# circuit_R2.net
KiCad netlist of a schematic drawn in EAGLE
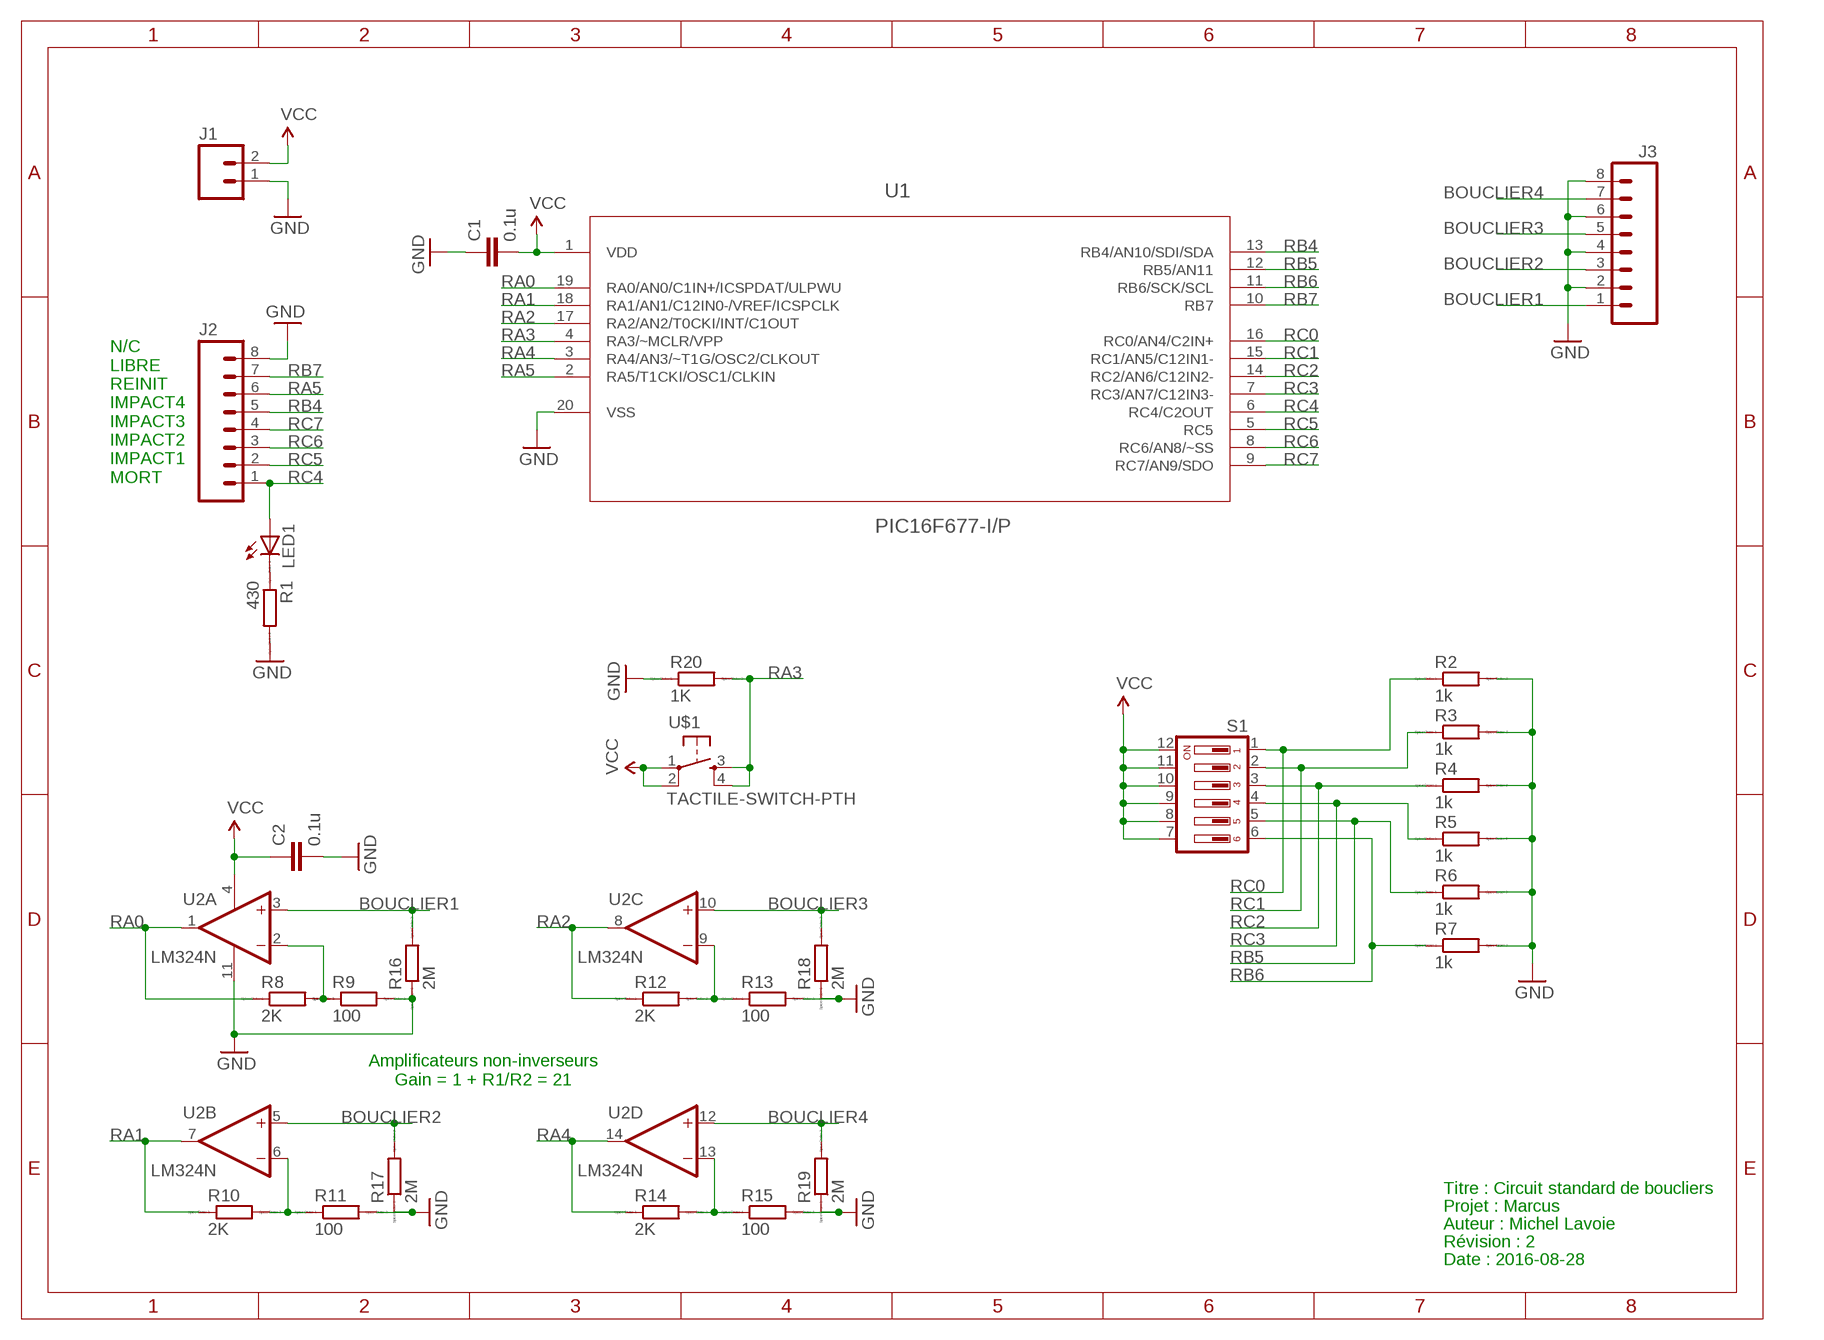
[diagram p0: schematic, sheet 1]

(export (version "E")
  (design (tool "Eeschema 10.0.6"))
  (components
    (comp (ref "C1")
      (value "0.1u")
      (footprint "eagle-import:CAP-PTH-SMALL")
      (libsource (lib "eagle-import") (part "CAPPTH"))
    )
    (comp (ref "C2")
      (value "0.1u")
      (footprint "eagle-import:CAP-PTH-SMALL")
      (libsource (lib "eagle-import") (part "CAPPTH"))
    )
    (comp (ref "J1")
      (value "M02PTH")
      (footprint "eagle-import:1X02")
      (libsource (lib "eagle-import") (part "M02PTH"))
    )
    (comp (ref "J2")
      (value "M08NO_SILK")
      (footprint "eagle-import:1X08_PIN1_NO_SILK")
      (libsource (lib "eagle-import") (part "M08NO_SILK"))
    )
    (comp (ref "J3")
      (value "M08NO_SILK")
      (footprint "eagle-import:1X08_PIN1_NO_SILK")
      (libsource (lib "eagle-import") (part "M08NO_SILK"))
    )
    (comp (ref "LED1")
      (value "LED3MM")
      (footprint "eagle-import:LED3MM")
      (libsource (lib "eagle-import") (part "LED3MM"))
    )
    (comp (ref "R1")
      (value "430")
      (footprint "eagle-import:0207_10")
      (libsource (lib "eagle-import") (part "R0207/10"))
    )
    (comp (ref "R2")
      (value "1k")
      (footprint "eagle-import:0207_10")
      (libsource (lib "eagle-import") (part "R0207/10"))
    )
    (comp (ref "R3")
      (value "1k")
      (footprint "eagle-import:0207_10")
      (libsource (lib "eagle-import") (part "R0207/10"))
    )
    (comp (ref "R4")
      (value "1k")
      (footprint "eagle-import:0207_10")
      (libsource (lib "eagle-import") (part "R0207/10"))
    )
    (comp (ref "R5")
      (value "1k")
      (footprint "eagle-import:0207_10")
      (libsource (lib "eagle-import") (part "R0207/10"))
    )
    (comp (ref "R6")
      (value "1k")
      (footprint "eagle-import:0207_10")
      (libsource (lib "eagle-import") (part "R0207/10"))
    )
    (comp (ref "R7")
      (value "1k")
      (footprint "eagle-import:0207_10")
      (libsource (lib "eagle-import") (part "R0207/10"))
    )
    (comp (ref "R8")
      (value "2K")
      (footprint "eagle-import:0207_10")
      (libsource (lib "eagle-import") (part "R0207/10"))
    )
    (comp (ref "R9")
      (value "100")
      (footprint "eagle-import:0207_10")
      (libsource (lib "eagle-import") (part "R0207/10"))
    )
    (comp (ref "R10")
      (value "2K")
      (footprint "eagle-import:0207_10")
      (libsource (lib "eagle-import") (part "R0207/10"))
    )
    (comp (ref "R11")
      (value "100")
      (footprint "eagle-import:0207_10")
      (libsource (lib "eagle-import") (part "R0207/10"))
    )
    (comp (ref "R12")
      (value "2K")
      (footprint "eagle-import:0207_10")
      (libsource (lib "eagle-import") (part "R0207/10"))
    )
    (comp (ref "R13")
      (value "100")
      (footprint "eagle-import:0207_10")
      (libsource (lib "eagle-import") (part "R0207/10"))
    )
    (comp (ref "R14")
      (value "2K")
      (footprint "eagle-import:0207_10")
      (libsource (lib "eagle-import") (part "R0207/10"))
    )
    (comp (ref "R15")
      (value "100")
      (footprint "eagle-import:0207_10")
      (libsource (lib "eagle-import") (part "R0207/10"))
    )
    (comp (ref "R16")
      (value "2M")
      (footprint "eagle-import:0207_10")
      (libsource (lib "eagle-import") (part "R0207/10"))
    )
    (comp (ref "R17")
      (value "2M")
      (footprint "eagle-import:0207_10")
      (libsource (lib "eagle-import") (part "R0207/10"))
    )
    (comp (ref "R18")
      (value "2M")
      (footprint "eagle-import:0207_10")
      (libsource (lib "eagle-import") (part "R0207/10"))
    )
    (comp (ref "R19")
      (value "2M")
      (footprint "eagle-import:0207_10")
      (libsource (lib "eagle-import") (part "R0207/10"))
    )
    (comp (ref "R20")
      (value "1K")
      (footprint "eagle-import:0207_10")
      (libsource (lib "eagle-import") (part "R0207/10"))
    )
    (comp (ref "S1")
      (value "DIP06YL")
      (footprint "eagle-import:DIP06YL")
      (libsource (lib "eagle-import") (part "DIP06YL"))
    )
    (comp (ref "U$1")
      (value "TACTILE-SWITCH-PTH")
      (footprint "eagle-import:TAC-SWITCH-PTH")
      (libsource (lib "eagle-import") (part "TACTILE-SWITCH-PTH"))
    )
    (comp (ref "U1")
      (value "PIC16F677-I/P")
      (footprint "eagle-import:DIP254P762X533-20")
      (libsource (lib "eagle-import") (part "PIC16F677-I/P"))
    )
    (comp (ref "U2")
      (value "LM324N")
      (footprint "eagle-import:DIL14")
      (libsource (lib "eagle-import") (part "LM324N"))
    )
  )
  (nets
    (net (code "1") (name "/BOUCLIER1") (class "Default")
      (node (ref "J3") (pin "1") (pinfunction "1_1") (pintype "passive"))
      (node (ref "R16") (pin "2") (pinfunction "2_2") (pintype "passive"))
      (node (ref "U2") (pin "3") (pinfunction "+IN_3") (pintype "input"))
    )
    (net (code "2") (name "/BOUCLIER2") (class "Default")
      (node (ref "J3") (pin "3") (pinfunction "3_3") (pintype "passive"))
      (node (ref "R17") (pin "2") (pinfunction "2_2") (pintype "passive"))
      (node (ref "U2") (pin "5") (pinfunction "+IN_5") (pintype "input"))
    )
    (net (code "3") (name "/BOUCLIER3") (class "Default")
      (node (ref "J3") (pin "5") (pinfunction "5_5") (pintype "passive"))
      (node (ref "R18") (pin "2") (pinfunction "2_2") (pintype "passive"))
      (node (ref "U2") (pin "10") (pinfunction "+IN_10") (pintype "input"))
    )
    (net (code "4") (name "/BOUCLIER4") (class "Default")
      (node (ref "J3") (pin "7") (pinfunction "7_7") (pintype "passive"))
      (node (ref "R19") (pin "2") (pinfunction "2_2") (pintype "passive"))
      (node (ref "U2") (pin "12") (pinfunction "+IN_12") (pintype "input"))
    )
    (net (code "5") (name "/RA0") (class "Default")
      (node (ref "R8") (pin "1") (pinfunction "1_1") (pintype "passive"))
      (node (ref "U1") (pin "19") (pinfunction "RA0/AN0/C1IN+/ICSPDAT/ULPWU_19") (pintype "bidirectional"))
      (node (ref "U2") (pin "1") (pinfunction "OUT_1") (pintype "output"))
    )
    (net (code "6") (name "/RA1") (class "Default")
      (node (ref "R10") (pin "1") (pinfunction "1_1") (pintype "passive"))
      (node (ref "U1") (pin "18") (pinfunction "RA1/AN1/C12IN0-/VREF/ICSPCLK_18") (pintype "bidirectional"))
      (node (ref "U2") (pin "7") (pinfunction "OUT_7") (pintype "output"))
    )
    (net (code "7") (name "/RA2") (class "Default")
      (node (ref "R12") (pin "1") (pinfunction "1_1") (pintype "passive"))
      (node (ref "U1") (pin "17") (pinfunction "RA2/AN2/T0CKI/INT/C1OUT_17") (pintype "bidirectional"))
      (node (ref "U2") (pin "8") (pinfunction "OUT_8") (pintype "output"))
    )
    (net (code "8") (name "/RA3") (class "Default")
      (node (ref "R20") (pin "2") (pinfunction "2_2") (pintype "passive"))
      (node (ref "U$1") (pin "3") (pinfunction "3_3") (pintype "passive"))
      (node (ref "U$1") (pin "4") (pinfunction "4_4") (pintype "passive"))
      (node (ref "U1") (pin "4") (pinfunction "RA3/~{MCLR/VPP}_4") (pintype "bidirectional"))
    )
    (net (code "9") (name "/RA4") (class "Default")
      (node (ref "R14") (pin "1") (pinfunction "1_1") (pintype "passive"))
      (node (ref "U1") (pin "3") (pinfunction "RA4/AN3/~{T1G/OSC2/CLKOUT}_3") (pintype "bidirectional"))
      (node (ref "U2") (pin "14") (pinfunction "OUT_14") (pintype "output"))
    )
    (net (code "10") (name "/RA5") (class "Default")
      (node (ref "J2") (pin "6") (pinfunction "6_6") (pintype "passive"))
      (node (ref "U1") (pin "2") (pinfunction "RA5/T1CKI/OSC1/CLKIN_2") (pintype "bidirectional"))
    )
    (net (code "11") (name "/RB4") (class "Default")
      (node (ref "J2") (pin "5") (pinfunction "5_5") (pintype "passive"))
      (node (ref "U1") (pin "13") (pinfunction "RB4/AN10/SDI/SDA_13") (pintype "bidirectional"))
    )
    (net (code "12") (name "/RB5") (class "Default")
      (node (ref "R6") (pin "1") (pinfunction "1_1") (pintype "passive"))
      (node (ref "S1") (pin "5") (pinfunction "5_5") (pintype "passive"))
      (node (ref "U1") (pin "12") (pinfunction "RB5/AN11_12") (pintype "bidirectional"))
    )
    (net (code "13") (name "/RB6") (class "Default")
      (node (ref "R7") (pin "1") (pinfunction "1_1") (pintype "passive"))
      (node (ref "S1") (pin "6") (pinfunction "6_6") (pintype "passive"))
      (node (ref "U1") (pin "11") (pinfunction "RB6/SCK/SCL_11") (pintype "bidirectional"))
    )
    (net (code "14") (name "/RB7") (class "Default")
      (node (ref "J2") (pin "7") (pinfunction "7_7") (pintype "passive"))
      (node (ref "U1") (pin "10") (pinfunction "RB7_10") (pintype "bidirectional"))
    )
    (net (code "15") (name "/RC0") (class "Default")
      (node (ref "R2") (pin "1") (pinfunction "1_1") (pintype "passive"))
      (node (ref "S1") (pin "1") (pinfunction "1_1") (pintype "passive"))
      (node (ref "U1") (pin "16") (pinfunction "RC0/AN4/C2IN+_16") (pintype "bidirectional"))
    )
    (net (code "16") (name "/RC1") (class "Default")
      (node (ref "R3") (pin "1") (pinfunction "1_1") (pintype "passive"))
      (node (ref "S1") (pin "2") (pinfunction "2_2") (pintype "passive"))
      (node (ref "U1") (pin "15") (pinfunction "RC1/AN5/C12IN1-_15") (pintype "bidirectional"))
    )
    (net (code "17") (name "/RC2") (class "Default")
      (node (ref "R4") (pin "1") (pinfunction "1_1") (pintype "passive"))
      (node (ref "S1") (pin "3") (pinfunction "3_3") (pintype "passive"))
      (node (ref "U1") (pin "14") (pinfunction "RC2/AN6/C12IN2-_14") (pintype "bidirectional"))
    )
    (net (code "18") (name "/RC3") (class "Default")
      (node (ref "R5") (pin "1") (pinfunction "1_1") (pintype "passive"))
      (node (ref "S1") (pin "4") (pinfunction "4_4") (pintype "passive"))
      (node (ref "U1") (pin "7") (pinfunction "RC3/AN7/C12IN3-_7") (pintype "bidirectional"))
    )
    (net (code "19") (name "/RC4") (class "Default")
      (node (ref "J2") (pin "1") (pinfunction "1_1") (pintype "passive"))
      (node (ref "LED1") (pin "A") (pinfunction "A_A") (pintype "passive"))
      (node (ref "U1") (pin "6") (pinfunction "RC4/C2OUT_6") (pintype "bidirectional"))
    )
    (net (code "20") (name "/RC5") (class "Default")
      (node (ref "J2") (pin "2") (pinfunction "2_2") (pintype "passive"))
      (node (ref "U1") (pin "5") (pinfunction "RC5_5") (pintype "bidirectional"))
    )
    (net (code "21") (name "/RC6") (class "Default")
      (node (ref "J2") (pin "3") (pinfunction "3_3") (pintype "passive"))
      (node (ref "U1") (pin "8") (pinfunction "RC6/AN8/~{SS}_8") (pintype "bidirectional"))
    )
    (net (code "22") (name "/RC7") (class "Default")
      (node (ref "J2") (pin "4") (pinfunction "4_4") (pintype "passive"))
      (node (ref "U1") (pin "9") (pinfunction "RC7/AN9/SDO_9") (pintype "bidirectional"))
    )
    (net (code "23") (name "GND") (class "Default")
      (node (ref "C1") (pin "1") (pinfunction "1_1") (pintype "passive"))
      (node (ref "C2") (pin "2") (pinfunction "2_2") (pintype "passive"))
      (node (ref "J1") (pin "1") (pinfunction "1_1") (pintype "passive"))
      (node (ref "J2") (pin "8") (pinfunction "8_8") (pintype "passive"))
      (node (ref "J3") (pin "2") (pinfunction "2_2") (pintype "passive"))
      (node (ref "J3") (pin "4") (pinfunction "4_4") (pintype "passive"))
      (node (ref "J3") (pin "6") (pinfunction "6_6") (pintype "passive"))
      (node (ref "J3") (pin "8") (pinfunction "8_8") (pintype "passive"))
      (node (ref "R1") (pin "2") (pinfunction "2_2") (pintype "passive"))
      (node (ref "R11") (pin "2") (pinfunction "2_2") (pintype "passive"))
      (node (ref "R13") (pin "2") (pinfunction "2_2") (pintype "passive"))
      (node (ref "R15") (pin "2") (pinfunction "2_2") (pintype "passive"))
      (node (ref "R16") (pin "1") (pinfunction "1_1") (pintype "passive"))
      (node (ref "R17") (pin "1") (pinfunction "1_1") (pintype "passive"))
      (node (ref "R18") (pin "1") (pinfunction "1_1") (pintype "passive"))
      (node (ref "R19") (pin "1") (pinfunction "1_1") (pintype "passive"))
      (node (ref "R2") (pin "2") (pinfunction "2_2") (pintype "passive"))
      (node (ref "R20") (pin "1") (pinfunction "1_1") (pintype "passive"))
      (node (ref "R3") (pin "2") (pinfunction "2_2") (pintype "passive"))
      (node (ref "R4") (pin "2") (pinfunction "2_2") (pintype "passive"))
      (node (ref "R5") (pin "2") (pinfunction "2_2") (pintype "passive"))
      (node (ref "R6") (pin "2") (pinfunction "2_2") (pintype "passive"))
      (node (ref "R7") (pin "2") (pinfunction "2_2") (pintype "passive"))
      (node (ref "R9") (pin "2") (pinfunction "2_2") (pintype "passive"))
      (node (ref "U1") (pin "20") (pinfunction "VSS_20") (pintype "power_in"))
      (node (ref "U2") (pin "11") (pinfunction "V-_11") (pintype "power_in"))
    )
    (net (code "24") (name "Net-(LED1-C)") (class "Default")
      (node (ref "LED1") (pin "K") (pinfunction "C_K") (pintype "passive"))
      (node (ref "R1") (pin "1") (pinfunction "1_1") (pintype "passive"))
    )
    (net (code "25") (name "Net-(U2A--IN)") (class "Default")
      (node (ref "R8") (pin "2") (pinfunction "2_2") (pintype "passive"))
      (node (ref "R9") (pin "1") (pinfunction "1_1") (pintype "passive"))
      (node (ref "U2") (pin "2") (pinfunction "-IN_2") (pintype "input"))
    )
    (net (code "26") (name "Net-(U2B--IN)") (class "Default")
      (node (ref "R10") (pin "2") (pinfunction "2_2") (pintype "passive"))
      (node (ref "R11") (pin "1") (pinfunction "1_1") (pintype "passive"))
      (node (ref "U2") (pin "6") (pinfunction "-IN_6") (pintype "input"))
    )
    (net (code "27") (name "Net-(U2C--IN)") (class "Default")
      (node (ref "R12") (pin "2") (pinfunction "2_2") (pintype "passive"))
      (node (ref "R13") (pin "1") (pinfunction "1_1") (pintype "passive"))
      (node (ref "U2") (pin "9") (pinfunction "-IN_9") (pintype "input"))
    )
    (net (code "28") (name "Net-(U2D--IN)") (class "Default")
      (node (ref "R14") (pin "2") (pinfunction "2_2") (pintype "passive"))
      (node (ref "R15") (pin "1") (pinfunction "1_1") (pintype "passive"))
      (node (ref "U2") (pin "13") (pinfunction "-IN_13") (pintype "input"))
    )
    (net (code "29") (name "VCC") (class "Default")
      (node (ref "C1") (pin "2") (pinfunction "2_2") (pintype "passive"))
      (node (ref "C2") (pin "1") (pinfunction "1_1") (pintype "passive"))
      (node (ref "J1") (pin "2") (pinfunction "2_2") (pintype "passive"))
      (node (ref "S1") (pin "10") (pinfunction "10_10") (pintype "passive"))
      (node (ref "S1") (pin "11") (pinfunction "11_11") (pintype "passive"))
      (node (ref "S1") (pin "12") (pinfunction "12_12") (pintype "passive"))
      (node (ref "S1") (pin "7") (pinfunction "7_7") (pintype "passive"))
      (node (ref "S1") (pin "8") (pinfunction "8_8") (pintype "passive"))
      (node (ref "S1") (pin "9") (pinfunction "9_9") (pintype "passive"))
      (node (ref "U$1") (pin "1") (pinfunction "1_1") (pintype "passive"))
      (node (ref "U$1") (pin "2") (pinfunction "2_2") (pintype "passive"))
      (node (ref "U1") (pin "1") (pinfunction "VDD_1") (pintype "power_in"))
      (node (ref "U2") (pin "4") (pinfunction "V+_4") (pintype "power_in"))
    )
  )
)
